# BSPD_revD.net
KiCad netlist of a schematic drawn in EAGLE
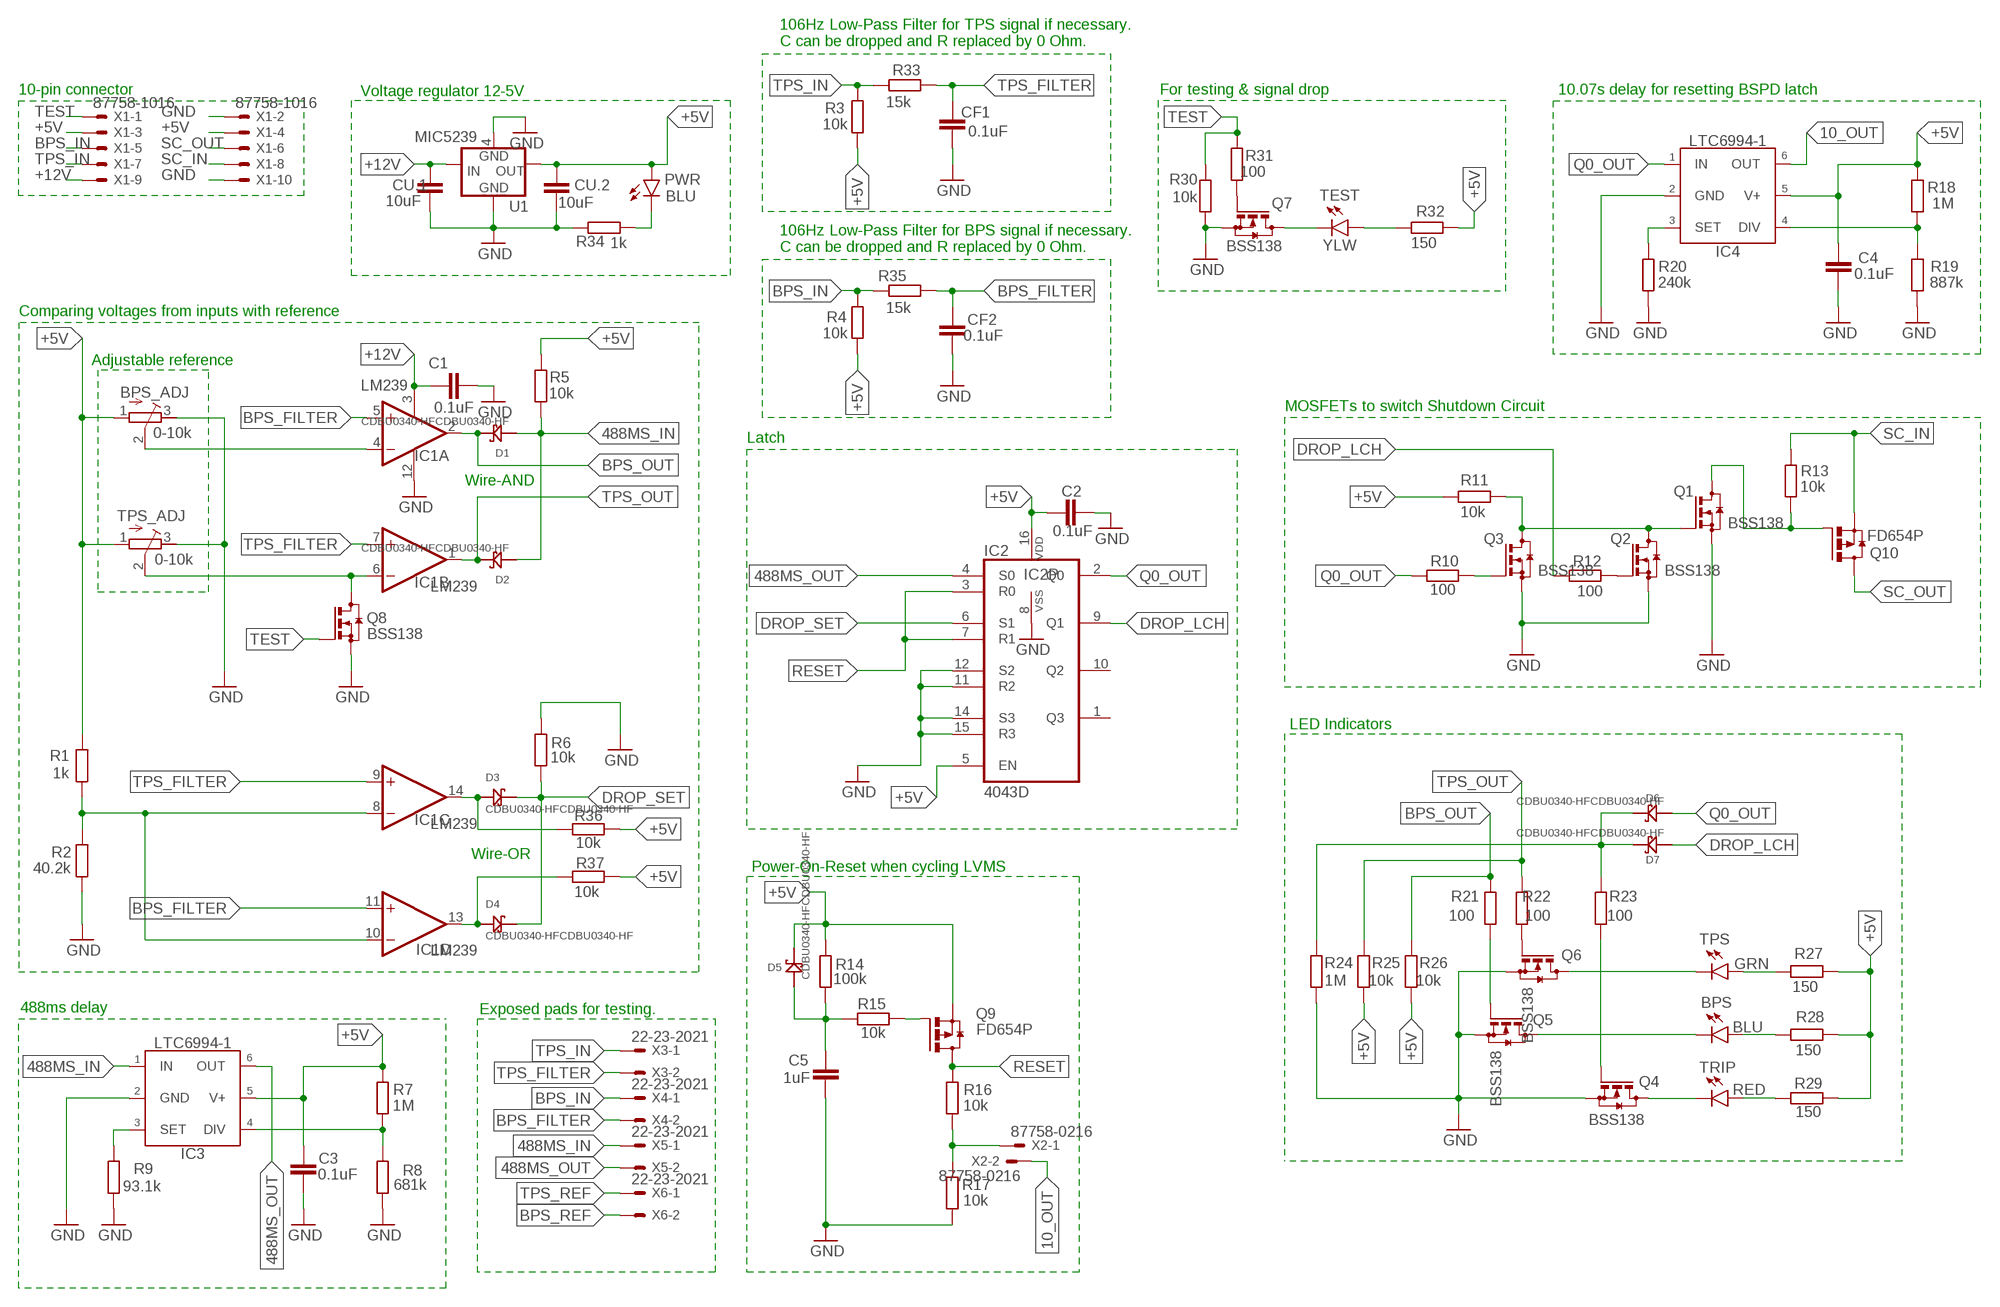
[diagram p0: schematic, sheet 1]

(export (version "E")
  (design (tool "Eeschema 10.0.6"))
  (components
    (comp (ref "BPS")
      (value "BLU")
      (footprint "eagle-import:SML1206")
      (libsource (lib "eagle-import") (part "LEDSML1206"))
    )
    (comp (ref "BPS_ADJ")
      (value "0-10k")
      (footprint "eagle-import:RTRIM3296W")
      (libsource (lib "eagle-import") (part "R-TRIMM3296W"))
    )
    (comp (ref "C1")
      (value "0.1uF")
      (footprint "eagle-import:C0603")
      (libsource (lib "eagle-import") (part "C-EUC0603"))
    )
    (comp (ref "C2")
      (value "0.1uF")
      (footprint "eagle-import:C0603")
      (libsource (lib "eagle-import") (part "C-EUC0603"))
    )
    (comp (ref "C3")
      (value "0.1uF")
      (footprint "eagle-import:C0603")
      (libsource (lib "eagle-import") (part "C-EUC0603"))
    )
    (comp (ref "C4")
      (value "0.1uF")
      (footprint "eagle-import:C0603")
      (libsource (lib "eagle-import") (part "C-EUC0603"))
    )
    (comp (ref "C5")
      (value "1uF")
      (footprint "eagle-import:C0603")
      (libsource (lib "eagle-import") (part "C-EUC0603"))
    )
    (comp (ref "CF1")
      (value "0.1uF")
      (footprint "eagle-import:C0603")
      (libsource (lib "eagle-import") (part "C-EUC0603"))
    )
    (comp (ref "CF2")
      (value "0.1uF")
      (footprint "eagle-import:C0603")
      (libsource (lib "eagle-import") (part "C-EUC0603"))
    )
    (comp (ref "CU.1")
      (value "10uF")
      (footprint "eagle-import:C0603")
      (libsource (lib "eagle-import") (part "C-EUC0603"))
    )
    (comp (ref "CU.2")
      (value "10uF")
      (footprint "eagle-import:C0603")
      (libsource (lib "eagle-import") (part "C-EUC0603"))
    )
    (comp (ref "D1")
      (value "CDBU0340-HFCDBU0340-HF")
      (footprint "eagle-import:DIOM1709X85")
      (libsource (lib "eagle-import") (part "CDBU0340-HFCDBU0340-HF"))
    )
    (comp (ref "D2")
      (value "CDBU0340-HFCDBU0340-HF")
      (footprint "eagle-import:DIOM1709X85")
      (libsource (lib "eagle-import") (part "CDBU0340-HFCDBU0340-HF"))
    )
    (comp (ref "D3")
      (value "CDBU0340-HFCDBU0340-HF")
      (footprint "eagle-import:DIOM1709X85")
      (libsource (lib "eagle-import") (part "CDBU0340-HFCDBU0340-HF"))
    )
    (comp (ref "D4")
      (value "CDBU0340-HFCDBU0340-HF")
      (footprint "eagle-import:DIOM1709X85")
      (libsource (lib "eagle-import") (part "CDBU0340-HFCDBU0340-HF"))
    )
    (comp (ref "D5")
      (value "CDBU0340-HFCDBU0340-HF")
      (footprint "eagle-import:DIOM1709X85")
      (libsource (lib "eagle-import") (part "CDBU0340-HFCDBU0340-HF"))
    )
    (comp (ref "D6")
      (value "CDBU0340-HFCDBU0340-HF")
      (footprint "eagle-import:DIOM1709X85")
      (libsource (lib "eagle-import") (part "CDBU0340-HFCDBU0340-HF"))
    )
    (comp (ref "D7")
      (value "CDBU0340-HFCDBU0340-HF")
      (footprint "eagle-import:DIOM1709X85")
      (libsource (lib "eagle-import") (part "CDBU0340-HFCDBU0340-HF"))
    )
    (comp (ref "IC1")
      (value "LM239")
      (footprint "eagle-import:SO14")
      (libsource (lib "eagle-import") (part "LM2901D"))
    )
    (comp (ref "IC2")
      (value "4043D")
      (footprint "eagle-import:SO16")
      (libsource (lib "eagle-import") (part "4043D"))
    )
    (comp (ref "IC3")
      (value "LTC6994-1")
      (footprint "eagle-import:TSOT23-6")
      (libsource (lib "eagle-import") (part "LTC6994-1"))
    )
    (comp (ref "IC4")
      (value "LTC6994-1")
      (footprint "eagle-import:TSOT23-6")
      (libsource (lib "eagle-import") (part "LTC6994-1"))
    )
    (comp (ref "PWR")
      (value "BLU")
      (footprint "eagle-import:SML1206")
      (libsource (lib "eagle-import") (part "LEDSML1206"))
    )
    (comp (ref "Q1")
      (value "BSS138")
      (footprint "eagle-import:SOT23")
      (libsource (lib "eagle-import") (part "BSS123"))
    )
    (comp (ref "Q2")
      (value "BSS138")
      (footprint "eagle-import:SOT23")
      (libsource (lib "eagle-import") (part "BSS123"))
    )
    (comp (ref "Q3")
      (value "BSS138")
      (footprint "eagle-import:SOT23")
      (libsource (lib "eagle-import") (part "BSS123"))
    )
    (comp (ref "Q4")
      (value "BSS138")
      (footprint "eagle-import:SOT23")
      (libsource (lib "eagle-import") (part "BSS123"))
    )
    (comp (ref "Q5")
      (value "BSS138")
      (footprint "eagle-import:SOT23")
      (libsource (lib "eagle-import") (part "BSS123"))
    )
    (comp (ref "Q6")
      (value "BSS138")
      (footprint "eagle-import:SOT23")
      (libsource (lib "eagle-import") (part "BSS123"))
    )
    (comp (ref "Q7")
      (value "BSS138")
      (footprint "eagle-import:SOT23")
      (libsource (lib "eagle-import") (part "BSS123"))
    )
    (comp (ref "Q8")
      (value "BSS138")
      (footprint "eagle-import:SOT23")
      (libsource (lib "eagle-import") (part "BSS123"))
    )
    (comp (ref "Q9")
      (value "FD654P")
      (footprint "eagle-import:SOT-23-6")
      (libsource (lib "eagle-import") (part "FD654P"))
    )
    (comp (ref "Q10")
      (value "FD654P")
      (footprint "eagle-import:SOT-23-6")
      (libsource (lib "eagle-import") (part "FD654P"))
    )
    (comp (ref "R1")
      (value "1k")
      (footprint "eagle-import:R0603")
      (libsource (lib "eagle-import") (part "R-EU_R0603"))
    )
    (comp (ref "R2")
      (value "40.2k")
      (footprint "eagle-import:R0603")
      (libsource (lib "eagle-import") (part "R-EU_R0603"))
    )
    (comp (ref "R3")
      (value "10k")
      (footprint "eagle-import:R0603")
      (libsource (lib "eagle-import") (part "R-EU_R0603"))
    )
    (comp (ref "R4")
      (value "10k")
      (footprint "eagle-import:R0603")
      (libsource (lib "eagle-import") (part "R-EU_R0603"))
    )
    (comp (ref "R5")
      (value "10k")
      (footprint "eagle-import:R0603")
      (libsource (lib "eagle-import") (part "R-EU_R0603"))
    )
    (comp (ref "R6")
      (value "10k")
      (footprint "eagle-import:R0603")
      (libsource (lib "eagle-import") (part "R-EU_R0603"))
    )
    (comp (ref "R7")
      (value "1M")
      (footprint "eagle-import:R0603")
      (libsource (lib "eagle-import") (part "R-EU_R0603"))
    )
    (comp (ref "R8")
      (value "681k")
      (footprint "eagle-import:R0603")
      (libsource (lib "eagle-import") (part "R-EU_R0603"))
    )
    (comp (ref "R9")
      (value "93.1k")
      (footprint "eagle-import:R0603")
      (libsource (lib "eagle-import") (part "R-EU_R0603"))
    )
    (comp (ref "R10")
      (value "100")
      (footprint "eagle-import:R0603")
      (libsource (lib "eagle-import") (part "R-EU_R0603"))
    )
    (comp (ref "R11")
      (value "10k")
      (footprint "eagle-import:R0603")
      (libsource (lib "eagle-import") (part "R-EU_R0603"))
    )
    (comp (ref "R12")
      (value "100")
      (footprint "eagle-import:R0603")
      (libsource (lib "eagle-import") (part "R-EU_R0603"))
    )
    (comp (ref "R13")
      (value "10k")
      (footprint "eagle-import:R0603")
      (libsource (lib "eagle-import") (part "R-EU_R0603"))
    )
    (comp (ref "R14")
      (value "100k")
      (footprint "eagle-import:R0603")
      (libsource (lib "eagle-import") (part "R-EU_R0603"))
    )
    (comp (ref "R15")
      (value "10k")
      (footprint "eagle-import:R0603")
      (libsource (lib "eagle-import") (part "R-EU_R0603"))
    )
    (comp (ref "R16")
      (value "10k")
      (footprint "eagle-import:R0603")
      (libsource (lib "eagle-import") (part "R-EU_R0603"))
    )
    (comp (ref "R17")
      (value "10k")
      (footprint "eagle-import:R0603")
      (libsource (lib "eagle-import") (part "R-EU_R0603"))
    )
    (comp (ref "R18")
      (value "1M")
      (footprint "eagle-import:R0603")
      (libsource (lib "eagle-import") (part "R-EU_R0603"))
    )
    (comp (ref "R19")
      (value "887k")
      (footprint "eagle-import:R0603")
      (libsource (lib "eagle-import") (part "R-EU_R0603"))
    )
    (comp (ref "R20")
      (value "240k")
      (footprint "eagle-import:R0603")
      (libsource (lib "eagle-import") (part "R-EU_R0603"))
    )
    (comp (ref "R21")
      (value "100")
      (footprint "eagle-import:R0603")
      (libsource (lib "eagle-import") (part "R-EU_R0603"))
    )
    (comp (ref "R22")
      (value "100")
      (footprint "eagle-import:R0603")
      (libsource (lib "eagle-import") (part "R-EU_R0603"))
    )
    (comp (ref "R23")
      (value "100")
      (footprint "eagle-import:R0603")
      (libsource (lib "eagle-import") (part "R-EU_R0603"))
    )
    (comp (ref "R24")
      (value "1M")
      (footprint "eagle-import:R0603")
      (libsource (lib "eagle-import") (part "R-EU_R0603"))
    )
    (comp (ref "R25")
      (value "10k")
      (footprint "eagle-import:R0603")
      (libsource (lib "eagle-import") (part "R-EU_R0603"))
    )
    (comp (ref "R26")
      (value "10k")
      (footprint "eagle-import:R0603")
      (libsource (lib "eagle-import") (part "R-EU_R0603"))
    )
    (comp (ref "R27")
      (value "150")
      (footprint "eagle-import:R0603")
      (libsource (lib "eagle-import") (part "R-EU_R0603"))
    )
    (comp (ref "R28")
      (value "150")
      (footprint "eagle-import:R0603")
      (libsource (lib "eagle-import") (part "R-EU_R0603"))
    )
    (comp (ref "R29")
      (value "150")
      (footprint "eagle-import:R0603")
      (libsource (lib "eagle-import") (part "R-EU_R0603"))
    )
    (comp (ref "R30")
      (value "10k")
      (footprint "eagle-import:R0603")
      (libsource (lib "eagle-import") (part "R-EU_R0603"))
    )
    (comp (ref "R31")
      (value "100")
      (footprint "eagle-import:R0603")
      (libsource (lib "eagle-import") (part "R-EU_R0603"))
    )
    (comp (ref "R32")
      (value "150")
      (footprint "eagle-import:R0603")
      (libsource (lib "eagle-import") (part "R-EU_R0603"))
    )
    (comp (ref "R33")
      (value "15k")
      (footprint "eagle-import:R0603")
      (libsource (lib "eagle-import") (part "R-EU_R0603"))
    )
    (comp (ref "R34")
      (value "1k")
      (footprint "eagle-import:R0603")
      (libsource (lib "eagle-import") (part "R-EU_R0603"))
    )
    (comp (ref "R35")
      (value "15k")
      (footprint "eagle-import:R0603")
      (libsource (lib "eagle-import") (part "R-EU_R0603"))
    )
    (comp (ref "R36")
      (value "10k")
      (footprint "eagle-import:R0603")
      (libsource (lib "eagle-import") (part "R-EU_R0603"))
    )
    (comp (ref "R37")
      (value "10k")
      (footprint "eagle-import:R0603")
      (libsource (lib "eagle-import") (part "R-EU_R0603"))
    )
    (comp (ref "TEST")
      (value "YLW")
      (footprint "eagle-import:SML1206")
      (libsource (lib "eagle-import") (part "LEDSML1206"))
    )
    (comp (ref "TPS")
      (value "GRN")
      (footprint "eagle-import:SML1206")
      (libsource (lib "eagle-import") (part "LEDSML1206"))
    )
    (comp (ref "TPS_ADJ")
      (value "0-10k")
      (footprint "eagle-import:RTRIM3296W")
      (libsource (lib "eagle-import") (part "R-TRIMM3296W"))
    )
    (comp (ref "TRIP")
      (value "RED")
      (footprint "eagle-import:SML1206")
      (libsource (lib "eagle-import") (part "LEDSML1206"))
    )
    (comp (ref "U1")
      (value "MIC5239")
      (footprint "eagle-import:SOT223")
      (libsource (lib "eagle-import") (part "MIC5239"))
    )
    (comp (ref "X1")
      (value "87758-1016")
      (footprint "eagle-import:87758-1016")
      (fields (field (name "MF") "MOLEX"))
      (libsource (lib "eagle-import") (part "87758-1016"))
    )
    (comp (ref "X2")
      (value "87758-0216")
      (footprint "eagle-import:87758-0216")
      (fields (field (name "MF") "MOLEX"))
      (libsource (lib "eagle-import") (part "87758-0216"))
    )
    (comp (ref "X3")
      (value "22-23-2021")
      (footprint "eagle-import:22-23-2021")
      (fields (field (name "MF") "MOLEX"))
      (libsource (lib "eagle-import") (part "22-23-2021"))
    )
    (comp (ref "X4")
      (value "22-23-2021")
      (footprint "eagle-import:22-23-2021")
      (fields (field (name "MF") "MOLEX"))
      (libsource (lib "eagle-import") (part "22-23-2021"))
    )
    (comp (ref "X5")
      (value "22-23-2021")
      (footprint "eagle-import:22-23-2021")
      (fields (field (name "MF") "MOLEX"))
      (libsource (lib "eagle-import") (part "22-23-2021"))
    )
    (comp (ref "X6")
      (value "22-23-2021")
      (footprint "eagle-import:22-23-2021")
      (fields (field (name "MF") "MOLEX"))
      (libsource (lib "eagle-import") (part "22-23-2021"))
    )
  )
  (nets
    (net (code "1") (name "+5V") (class "Default")
      (node (ref "BPS_ADJ") (pin "1") (pinfunction "A_1") (pintype "passive"))
      (node (ref "C2") (pin "1") (pinfunction "1_1") (pintype "passive"))
      (node (ref "C3") (pin "2") (pinfunction "2_2") (pintype "passive"))
      (node (ref "C4") (pin "2") (pinfunction "2_2") (pintype "passive"))
      (node (ref "CU.2") (pin "1") (pinfunction "1_1") (pintype "passive"))
      (node (ref "D5") (pin "1$K") (pinfunction "K_1$K") (pintype "input"))
      (node (ref "IC2") (pin "16") (pinfunction "VDD_16") (pintype "power_in"))
      (node (ref "IC2") (pin "5") (pinfunction "EN_5") (pintype "input"))
      (node (ref "IC3") (pin "5") (pinfunction "V+_5") (pintype "passive"))
      (node (ref "IC4") (pin "5") (pinfunction "V+_5") (pintype "passive"))
      (node (ref "PWR") (pin "A") (pinfunction "A_A") (pintype "passive"))
      (node (ref "Q9") (pin "4") (pinfunction "S_4") (pintype "passive"))
      (node (ref "R1") (pin "2") (pinfunction "2_2") (pintype "passive"))
      (node (ref "R11") (pin "2") (pinfunction "2_2") (pintype "passive"))
      (node (ref "R14") (pin "2") (pinfunction "2_2") (pintype "passive"))
      (node (ref "R18") (pin "2") (pinfunction "2_2") (pintype "passive"))
      (node (ref "R25") (pin "1") (pinfunction "1_1") (pintype "passive"))
      (node (ref "R26") (pin "1") (pinfunction "1_1") (pintype "passive"))
      (node (ref "R27") (pin "2") (pinfunction "2_2") (pintype "passive"))
      (node (ref "R28") (pin "2") (pinfunction "2_2") (pintype "passive"))
      (node (ref "R29") (pin "2") (pinfunction "2_2") (pintype "passive"))
      (node (ref "R3") (pin "1") (pinfunction "1_1") (pintype "passive"))
      (node (ref "R32") (pin "2") (pinfunction "2_2") (pintype "passive"))
      (node (ref "R36") (pin "1") (pinfunction "1_1") (pintype "passive"))
      (node (ref "R37") (pin "1") (pinfunction "1_1") (pintype "passive"))
      (node (ref "R4") (pin "1") (pinfunction "1_1") (pintype "passive"))
      (node (ref "R5") (pin "2") (pinfunction "2_2") (pintype "passive"))
      (node (ref "R7") (pin "2") (pinfunction "2_2") (pintype "passive"))
      (node (ref "TPS_ADJ") (pin "1") (pinfunction "A_1") (pintype "passive"))
      (node (ref "U1") (pin "3") (pinfunction "OUT_3") (pintype "passive"))
      (node (ref "X1") (pin "3") (pinfunction "S_3") (pintype "passive"))
      (node (ref "X1") (pin "4") (pinfunction "S_4") (pintype "passive"))
    )
    (net (code "2") (name "+12V") (class "Default")
      (node (ref "C1") (pin "1") (pinfunction "1_1") (pintype "passive"))
      (node (ref "CU.1") (pin "1") (pinfunction "1_1") (pintype "passive"))
      (node (ref "IC1") (pin "3") (pinfunction "V+_3") (pintype "power_in"))
      (node (ref "U1") (pin "1") (pinfunction "IN_1") (pintype "input"))
      (node (ref "X1") (pin "9") (pinfunction "S_9") (pintype "passive"))
    )
    (net (code "3") (name "10_OUT") (class "Default")
      (node (ref "IC4") (pin "6") (pinfunction "OUT_6") (pintype "passive"))
      (node (ref "X2") (pin "2") (pinfunction "S_2") (pintype "passive"))
    )
    (net (code "4") (name "488MS_IN") (class "Default")
      (node (ref "D1") (pin "2$A") (pinfunction "A_2$A") (pintype "input"))
      (node (ref "D2") (pin "2$A") (pinfunction "A_2$A") (pintype "input"))
      (node (ref "IC3") (pin "1") (pinfunction "IN_1") (pintype "passive"))
      (node (ref "R5") (pin "1") (pinfunction "1_1") (pintype "passive"))
      (node (ref "X5") (pin "1") (pinfunction "S_1") (pintype "passive"))
    )
    (net (code "5") (name "488MS_OUT") (class "Default")
      (node (ref "IC2") (pin "4") (pinfunction "S0_4") (pintype "input"))
      (node (ref "IC3") (pin "6") (pinfunction "OUT_6") (pintype "passive"))
      (node (ref "X5") (pin "2") (pinfunction "S_2") (pintype "passive"))
    )
    (net (code "6") (name "BPS_FILTER") (class "Default")
      (node (ref "CF2") (pin "2") (pinfunction "2_2") (pintype "passive"))
      (node (ref "IC1") (pin "11") (pinfunction "+IN_11") (pintype "input"))
      (node (ref "IC1") (pin "5") (pinfunction "+IN_5") (pintype "input"))
      (node (ref "R35") (pin "1") (pinfunction "1_1") (pintype "passive"))
      (node (ref "X4") (pin "2") (pinfunction "S_2") (pintype "passive"))
    )
    (net (code "7") (name "BPS_IN") (class "Default")
      (node (ref "R35") (pin "2") (pinfunction "2_2") (pintype "passive"))
      (node (ref "R4") (pin "2") (pinfunction "2_2") (pintype "passive"))
      (node (ref "X1") (pin "5") (pinfunction "S_5") (pintype "passive"))
      (node (ref "X4") (pin "1") (pinfunction "S_1") (pintype "passive"))
    )
    (net (code "8") (name "BPS_OUT") (class "Default")
      (node (ref "D1") (pin "1$K") (pinfunction "K_1$K") (pintype "input"))
      (node (ref "IC1") (pin "2") (pinfunction "OUT_2") (pintype "output"))
      (node (ref "R21") (pin "2") (pinfunction "2_2") (pintype "passive"))
      (node (ref "R26") (pin "2") (pinfunction "2_2") (pintype "passive"))
    )
    (net (code "9") (name "BPS_REF") (class "Default")
      (node (ref "BPS_ADJ") (pin "2") (pinfunction "S_2") (pintype "passive"))
      (node (ref "IC1") (pin "4") (pinfunction "-IN_4") (pintype "input"))
      (node (ref "X6") (pin "2") (pinfunction "S_2") (pintype "passive"))
    )
    (net (code "10") (name "DROP_LCH") (class "Default")
      (node (ref "D7") (pin "2$A") (pinfunction "A_2$A") (pintype "input"))
      (node (ref "IC2") (pin "9") (pinfunction "Q1_9") (pintype "output"))
      (node (ref "R12") (pin "2") (pinfunction "2_2") (pintype "passive"))
    )
    (net (code "11") (name "DROP_SET") (class "Default")
      (node (ref "D3") (pin "1$K") (pinfunction "K_1$K") (pintype "input"))
      (node (ref "D4") (pin "1$K") (pinfunction "K_1$K") (pintype "input"))
      (node (ref "IC2") (pin "6") (pinfunction "S1_6") (pintype "input"))
      (node (ref "R6") (pin "1") (pinfunction "1_1") (pintype "passive"))
    )
    (net (code "12") (name "GND") (class "Default")
      (node (ref "BPS_ADJ") (pin "3") (pinfunction "E_3") (pintype "passive"))
      (node (ref "C1") (pin "2") (pinfunction "2_2") (pintype "passive"))
      (node (ref "C2") (pin "2") (pinfunction "2_2") (pintype "passive"))
      (node (ref "C3") (pin "1") (pinfunction "1_1") (pintype "passive"))
      (node (ref "C4") (pin "1") (pinfunction "1_1") (pintype "passive"))
      (node (ref "C5") (pin "1") (pinfunction "1_1") (pintype "passive"))
      (node (ref "CF1") (pin "1") (pinfunction "1_1") (pintype "passive"))
      (node (ref "CF2") (pin "1") (pinfunction "1_1") (pintype "passive"))
      (node (ref "CU.1") (pin "2") (pinfunction "2_2") (pintype "passive"))
      (node (ref "CU.2") (pin "2") (pinfunction "2_2") (pintype "passive"))
      (node (ref "IC1") (pin "12") (pinfunction "V-_12") (pintype "power_in"))
      (node (ref "IC2") (pin "11") (pinfunction "R2_11") (pintype "input"))
      (node (ref "IC2") (pin "12") (pinfunction "S2_12") (pintype "input"))
      (node (ref "IC2") (pin "14") (pinfunction "S3_14") (pintype "input"))
      (node (ref "IC2") (pin "15") (pinfunction "R3_15") (pintype "input"))
      (node (ref "IC2") (pin "8") (pinfunction "VSS_8") (pintype "power_in"))
      (node (ref "IC3") (pin "2") (pinfunction "GND_2") (pintype "passive"))
      (node (ref "IC4") (pin "2") (pinfunction "GND_2") (pintype "passive"))
      (node (ref "Q1") (pin "2") (pinfunction "S_2") (pintype "passive"))
      (node (ref "Q2") (pin "2") (pinfunction "S_2") (pintype "passive"))
      (node (ref "Q3") (pin "2") (pinfunction "S_2") (pintype "passive"))
      (node (ref "Q4") (pin "2") (pinfunction "S_2") (pintype "passive"))
      (node (ref "Q5") (pin "2") (pinfunction "S_2") (pintype "passive"))
      (node (ref "Q6") (pin "2") (pinfunction "S_2") (pintype "passive"))
      (node (ref "Q7") (pin "2") (pinfunction "S_2") (pintype "passive"))
      (node (ref "Q8") (pin "2") (pinfunction "S_2") (pintype "passive"))
      (node (ref "R17") (pin "2") (pinfunction "2_2") (pintype "passive"))
      (node (ref "R19") (pin "1") (pinfunction "1_1") (pintype "passive"))
      (node (ref "R2") (pin "1") (pinfunction "1_1") (pintype "passive"))
      (node (ref "R20") (pin "1") (pinfunction "1_1") (pintype "passive"))
      (node (ref "R24") (pin "1") (pinfunction "1_1") (pintype "passive"))
      (node (ref "R30") (pin "1") (pinfunction "1_1") (pintype "passive"))
      (node (ref "R34") (pin "1") (pinfunction "1_1") (pintype "passive"))
      (node (ref "R6") (pin "2") (pinfunction "2_2") (pintype "passive"))
      (node (ref "R8") (pin "1") (pinfunction "1_1") (pintype "passive"))
      (node (ref "R9") (pin "1") (pinfunction "1_1") (pintype "passive"))
      (node (ref "TPS_ADJ") (pin "3") (pinfunction "E_3") (pintype "passive"))
      (node (ref "U1") (pin "2") (pinfunction "GND_2") (pintype "input"))
      (node (ref "U1") (pin "4") (pinfunction "GND_TAB_4") (pintype "input"))
      (node (ref "X1") (pin "10") (pinfunction "S_10") (pintype "passive"))
      (node (ref "X1") (pin "2") (pinfunction "S_2") (pintype "passive"))
    )
    (net (code "13") (name "Net-(BPS-PadA)") (class "Default")
      (node (ref "BPS") (pin "A") (pinfunction "A_A") (pintype "passive"))
      (node (ref "R28") (pin "1") (pinfunction "1_1") (pintype "passive"))
    )
    (net (code "14") (name "Net-(D3-A)") (class "Default")
      (node (ref "D3") (pin "2$A") (pinfunction "A_2$A") (pintype "input"))
      (node (ref "IC1") (pin "14") (pinfunction "OUT_14") (pintype "output"))
      (node (ref "R36") (pin "2") (pinfunction "2_2") (pintype "passive"))
    )
    (net (code "15") (name "Net-(D4-A)") (class "Default")
      (node (ref "D4") (pin "2$A") (pinfunction "A_2$A") (pintype "input"))
      (node (ref "IC1") (pin "13") (pinfunction "OUT_13") (pintype "output"))
      (node (ref "R37") (pin "2") (pinfunction "2_2") (pintype "passive"))
    )
    (net (code "16") (name "Net-(D5-A)") (class "Default")
      (node (ref "C5") (pin "2") (pinfunction "2_2") (pintype "passive"))
      (node (ref "D5") (pin "2$A") (pinfunction "A_2$A") (pintype "input"))
      (node (ref "R14") (pin "1") (pinfunction "1_1") (pintype "passive"))
      (node (ref "R15") (pin "2") (pinfunction "2_2") (pintype "passive"))
    )
    (net (code "17") (name "Net-(D6-K)") (class "Default")
      (node (ref "D6") (pin "1$K") (pinfunction "K_1$K") (pintype "input"))
      (node (ref "D7") (pin "1$K") (pinfunction "K_1$K") (pintype "input"))
      (node (ref "R23") (pin "2") (pinfunction "2_2") (pintype "passive"))
      (node (ref "R24") (pin "2") (pinfunction "2_2") (pintype "passive"))
    )
    (net (code "18") (name "Net-(IC1C--IN)") (class "Default")
      (node (ref "IC1") (pin "10") (pinfunction "-IN_10") (pintype "input"))
      (node (ref "IC1") (pin "8") (pinfunction "-IN_8") (pintype "input"))
      (node (ref "R1") (pin "1") (pinfunction "1_1") (pintype "passive"))
      (node (ref "R2") (pin "2") (pinfunction "2_2") (pintype "passive"))
    )
    (net (code "19") (name "Net-(IC3-DIV)") (class "Default")
      (node (ref "IC3") (pin "4") (pinfunction "DIV_4") (pintype "passive"))
      (node (ref "R7") (pin "1") (pinfunction "1_1") (pintype "passive"))
      (node (ref "R8") (pin "2") (pinfunction "2_2") (pintype "passive"))
    )
    (net (code "20") (name "Net-(IC3-SET)") (class "Default")
      (node (ref "IC3") (pin "3") (pinfunction "SET_3") (pintype "passive"))
      (node (ref "R9") (pin "2") (pinfunction "2_2") (pintype "passive"))
    )
    (net (code "21") (name "Net-(IC4-DIV)") (class "Default")
      (node (ref "IC4") (pin "4") (pinfunction "DIV_4") (pintype "passive"))
      (node (ref "R18") (pin "1") (pinfunction "1_1") (pintype "passive"))
      (node (ref "R19") (pin "2") (pinfunction "2_2") (pintype "passive"))
    )
    (net (code "22") (name "Net-(IC4-SET)") (class "Default")
      (node (ref "IC4") (pin "3") (pinfunction "SET_3") (pintype "passive"))
      (node (ref "R20") (pin "2") (pinfunction "2_2") (pintype "passive"))
    )
    (net (code "23") (name "Net-(PWR-PadC)") (class "Default")
      (node (ref "PWR") (pin "C") (pinfunction "C_C") (pintype "passive"))
      (node (ref "R34") (pin "2") (pinfunction "2_2") (pintype "passive"))
    )
    (net (code "24") (name "Net-(Q1-D)") (class "Default")
      (node (ref "Q1") (pin "3") (pinfunction "D_3") (pintype "passive"))
      (node (ref "Q10") (pin "3") (pinfunction "G_3") (pintype "passive"))
      (node (ref "R13") (pin "2") (pinfunction "2_2") (pintype "passive"))
    )
    (net (code "25") (name "Net-(Q1-G)") (class "Default")
      (node (ref "Q1") (pin "1") (pinfunction "G_1") (pintype "passive"))
      (node (ref "Q2") (pin "3") (pinfunction "D_3") (pintype "passive"))
      (node (ref "Q3") (pin "3") (pinfunction "D_3") (pintype "passive"))
      (node (ref "R11") (pin "1") (pinfunction "1_1") (pintype "passive"))
    )
    (net (code "26") (name "Net-(Q2-G)") (class "Default")
      (node (ref "Q2") (pin "1") (pinfunction "G_1") (pintype "passive"))
      (node (ref "R12") (pin "1") (pinfunction "1_1") (pintype "passive"))
    )
    (net (code "27") (name "Net-(Q3-G)") (class "Default")
      (node (ref "Q3") (pin "1") (pinfunction "G_1") (pintype "passive"))
      (node (ref "R10") (pin "2") (pinfunction "2_2") (pintype "passive"))
    )
    (net (code "28") (name "Net-(Q4-D)") (class "Default")
      (node (ref "Q4") (pin "3") (pinfunction "D_3") (pintype "passive"))
      (node (ref "TRIP") (pin "C") (pinfunction "C_C") (pintype "passive"))
    )
    (net (code "29") (name "Net-(Q4-G)") (class "Default")
      (node (ref "Q4") (pin "1") (pinfunction "G_1") (pintype "passive"))
      (node (ref "R23") (pin "1") (pinfunction "1_1") (pintype "passive"))
    )
    (net (code "30") (name "Net-(Q5-D)") (class "Default")
      (node (ref "BPS") (pin "C") (pinfunction "C_C") (pintype "passive"))
      (node (ref "Q5") (pin "3") (pinfunction "D_3") (pintype "passive"))
    )
    (net (code "31") (name "Net-(Q5-G)") (class "Default")
      (node (ref "Q5") (pin "1") (pinfunction "G_1") (pintype "passive"))
      (node (ref "R21") (pin "1") (pinfunction "1_1") (pintype "passive"))
    )
    (net (code "32") (name "Net-(Q6-D)") (class "Default")
      (node (ref "Q6") (pin "3") (pinfunction "D_3") (pintype "passive"))
      (node (ref "TPS") (pin "C") (pinfunction "C_C") (pintype "passive"))
    )
    (net (code "33") (name "Net-(Q6-G)") (class "Default")
      (node (ref "Q6") (pin "1") (pinfunction "G_1") (pintype "passive"))
      (node (ref "R22") (pin "1") (pinfunction "1_1") (pintype "passive"))
    )
    (net (code "34") (name "Net-(Q7-D)") (class "Default")
      (node (ref "Q7") (pin "3") (pinfunction "D_3") (pintype "passive"))
      (node (ref "TEST") (pin "C") (pinfunction "C_C") (pintype "passive"))
    )
    (net (code "35") (name "Net-(Q7-G)") (class "Default")
      (node (ref "Q7") (pin "1") (pinfunction "G_1") (pintype "passive"))
      (node (ref "R31") (pin "1") (pinfunction "1_1") (pintype "passive"))
    )
    (net (code "36") (name "Net-(Q9-G)") (class "Default")
      (node (ref "Q9") (pin "3") (pinfunction "G_3") (pintype "passive"))
      (node (ref "R15") (pin "1") (pinfunction "1_1") (pintype "passive"))
    )
    (net (code "37") (name "Net-(R27-Pad1)") (class "Default")
      (node (ref "R27") (pin "1") (pinfunction "1_1") (pintype "passive"))
      (node (ref "TPS") (pin "A") (pinfunction "A_A") (pintype "passive"))
    )
    (net (code "38") (name "Net-(R29-Pad1)") (class "Default")
      (node (ref "R29") (pin "1") (pinfunction "1_1") (pintype "passive"))
      (node (ref "TRIP") (pin "A") (pinfunction "A_A") (pintype "passive"))
    )
    (net (code "39") (name "Net-(R32-Pad1)") (class "Default")
      (node (ref "R32") (pin "1") (pinfunction "1_1") (pintype "passive"))
      (node (ref "TEST") (pin "A") (pinfunction "A_A") (pintype "passive"))
    )
    (net (code "40") (name "Net-(X2A-S)") (class "Default")
      (node (ref "R16") (pin "2") (pinfunction "2_2") (pintype "passive"))
      (node (ref "R17") (pin "1") (pinfunction "1_1") (pintype "passive"))
      (node (ref "X2") (pin "1") (pinfunction "S_1") (pintype "passive"))
    )
    (net (code "41") (name "Q0_OUT") (class "Default")
      (node (ref "D6") (pin "2$A") (pinfunction "A_2$A") (pintype "input"))
      (node (ref "IC2") (pin "2") (pinfunction "Q0_2") (pintype "output"))
      (node (ref "IC4") (pin "1") (pinfunction "IN_1") (pintype "passive"))
      (node (ref "R10") (pin "1") (pinfunction "1_1") (pintype "passive"))
    )
    (net (code "42") (name "RESET") (class "Default")
      (node (ref "IC2") (pin "3") (pinfunction "R0_3") (pintype "input"))
      (node (ref "IC2") (pin "7") (pinfunction "R1_7") (pintype "input"))
      (node (ref "Q9") (pin "1") (pinfunction "D_1") (pintype "passive"))
      (node (ref "Q9") (pin "2") (pinfunction "D_2") (pintype "passive"))
      (node (ref "Q9") (pin "5") (pinfunction "D_5") (pintype "passive"))
      (node (ref "Q9") (pin "6") (pinfunction "D_6") (pintype "passive"))
      (node (ref "R16") (pin "1") (pinfunction "1_1") (pintype "passive"))
    )
    (net (code "43") (name "SC_IN") (class "Default")
      (node (ref "Q10") (pin "4") (pinfunction "S_4") (pintype "passive"))
      (node (ref "R13") (pin "1") (pinfunction "1_1") (pintype "passive"))
      (node (ref "X1") (pin "8") (pinfunction "S_8") (pintype "passive"))
    )
    (net (code "44") (name "SC_OUT") (class "Default")
      (node (ref "Q10") (pin "1") (pinfunction "D_1") (pintype "passive"))
      (node (ref "Q10") (pin "2") (pinfunction "D_2") (pintype "passive"))
      (node (ref "Q10") (pin "5") (pinfunction "D_5") (pintype "passive"))
      (node (ref "Q10") (pin "6") (pinfunction "D_6") (pintype "passive"))
      (node (ref "X1") (pin "6") (pinfunction "S_6") (pintype "passive"))
    )
    (net (code "45") (name "TEST") (class "Default")
      (node (ref "Q8") (pin "1") (pinfunction "G_1") (pintype "passive"))
      (node (ref "R30") (pin "2") (pinfunction "2_2") (pintype "passive"))
      (node (ref "R31") (pin "2") (pinfunction "2_2") (pintype "passive"))
      (node (ref "X1") (pin "1") (pinfunction "S_1") (pintype "passive"))
    )
    (net (code "46") (name "TPS_FILTER") (class "Default")
      (node (ref "CF1") (pin "2") (pinfunction "2_2") (pintype "passive"))
      (node (ref "IC1") (pin "7") (pinfunction "+IN_7") (pintype "input"))
      (node (ref "IC1") (pin "9") (pinfunction "+IN_9") (pintype "input"))
      (node (ref "R33") (pin "1") (pinfunction "1_1") (pintype "passive"))
      (node (ref "X3") (pin "2") (pinfunction "S_2") (pintype "passive"))
    )
    (net (code "47") (name "TPS_IN") (class "Default")
      (node (ref "R3") (pin "2") (pinfunction "2_2") (pintype "passive"))
      (node (ref "R33") (pin "2") (pinfunction "2_2") (pintype "passive"))
      (node (ref "X1") (pin "7") (pinfunction "S_7") (pintype "passive"))
      (node (ref "X3") (pin "1") (pinfunction "S_1") (pintype "passive"))
    )
    (net (code "48") (name "TPS_OUT") (class "Default")
      (node (ref "D2") (pin "1$K") (pinfunction "K_1$K") (pintype "input"))
      (node (ref "IC1") (pin "1") (pinfunction "OUT_1") (pintype "output"))
      (node (ref "R22") (pin "2") (pinfunction "2_2") (pintype "passive"))
      (node (ref "R25") (pin "2") (pinfunction "2_2") (pintype "passive"))
    )
    (net (code "49") (name "TPS_REF") (class "Default")
      (node (ref "IC1") (pin "6") (pinfunction "-IN_6") (pintype "input"))
      (node (ref "Q8") (pin "3") (pinfunction "D_3") (pintype "passive"))
      (node (ref "TPS_ADJ") (pin "2") (pinfunction "S_2") (pintype "passive"))
      (node (ref "X6") (pin "1") (pinfunction "S_1") (pintype "passive"))
    )
    (net (code "50") (name "unconnected-(IC2A-Q2-Pad10)") (class "Default")
      (node (ref "IC2") (pin "10") (pinfunction "Q2_10") (pintype "output"))
    )
    (net (code "51") (name "unconnected-(IC2A-Q3-Pad1)") (class "Default")
      (node (ref "IC2") (pin "1") (pinfunction "Q3_1") (pintype "output"))
    )
  )
)
